# BaseNode.net
KiCad netlist of a schematic drawn in Altium Designer
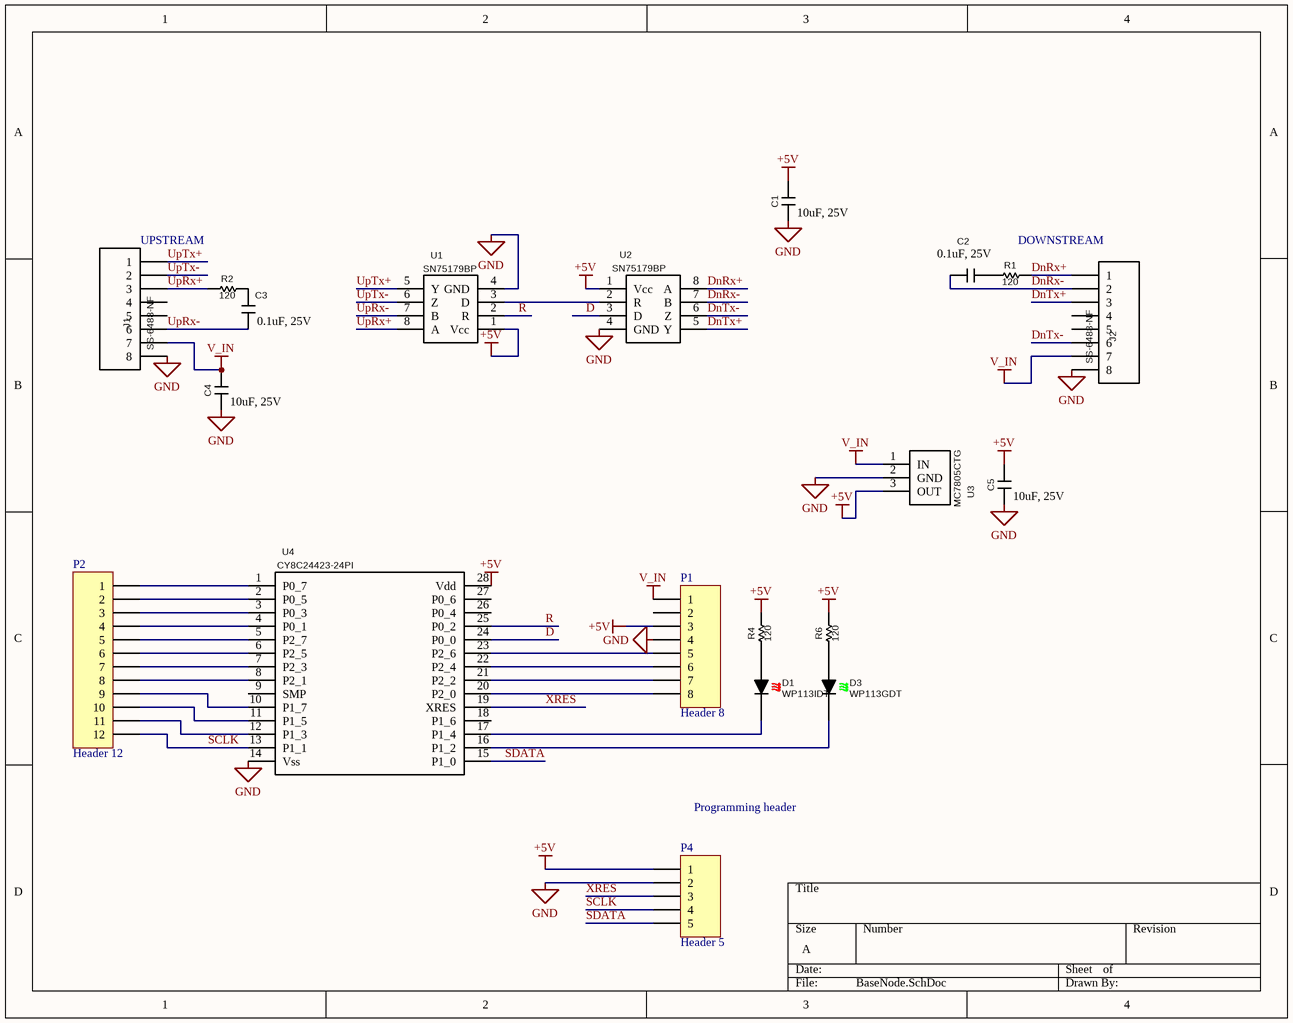
[diagram p0: BaseNode.SchDoc]

(export (version "E")
  (design (tool "Eeschema 10.0.6"))
  (components
    (comp (ref "C1")
      (value "10uF, 25V")
      (footprint "whong:Capacitor TH 0.2")
      (description "Capacitor")
      (fields (field (name "MANUFACTURER") "TDK Corporation"))
      (libsource (lib "whong") (part "Capacitor"))
    )
    (comp (ref "C2")
      (value "0.1uF, 25V")
      (footprint "whong:Capacitor TH 0.2")
      (description "Capacitor")
      (fields (field (name "MANUFACTURER") "Murata Electronics North America"))
      (libsource (lib "whong") (part "Capacitor"))
    )
    (comp (ref "C3")
      (value "0.1uF, 25V")
      (footprint "whong:Capacitor TH 0.2")
      (description "Capacitor")
      (fields (field (name "MANUFACTURER") "Murata Electronics North America"))
      (libsource (lib "whong") (part "Capacitor"))
    )
    (comp (ref "C4")
      (value "10uF, 25V")
      (footprint "whong:Capacitor TH 0.2")
      (description "Capacitor")
      (fields (field (name "MANUFACTURER") "TDK Corporation"))
      (libsource (lib "whong") (part "Capacitor"))
    )
    (comp (ref "C5")
      (value "10uF, 25V")
      (footprint "whong:Capacitor TH 0.2")
      (description "Capacitor")
      (fields (field (name "MANUFACTURER") "TDK Corporation"))
      (libsource (lib "whong") (part "Capacitor"))
    )
    (comp (ref "D1")
      (value "WP113IDT")
      (footprint "whong:LED 100mil")
      (description "LED RECT 2X5MM 625NM RED DIFF")
      (fields (field (name "MANUFACTURER") "Kingbright Corp") (field (name "MANUFACTURERPN") "WP113IDT"))
      (libsource (lib "whong") (part "WP113IDT"))
    )
    (comp (ref "D3")
      (value "WP113GDT")
      (footprint "whong:LED 100mil")
      (description "LED RECT 2X5MM 568NM GRN DIFF")
      (fields (field (name "MANUFACTURER") "Kingbright Corp") (field (name "MANUFACTURERPN") "WP113GDT"))
      (libsource (lib "whong") (part "WP113GDT"))
    )
    (comp (ref "J1")
      (value "SS-6488-NF")
      (footprint "whong:SS-6488-NF")
      (description "CONN 8-8 MOD JACK")
      (fields (field (name "MANUFACTURER") "Stewart Connector"))
      (libsource (lib "whong") (part "SS-6488-NF"))
    )
    (comp (ref "J2")
      (value "SS-6488-NF")
      (footprint "whong:SS-6488-NF")
      (description "CONN 8-8 MOD JACK")
      (fields (field (name "MANUFACTURER") "Stewart Connector"))
      (libsource (lib "") (part "SS-6488-NF_1"))
    )
    (comp (ref "P1")
      (value "Header 8")
      (footprint "HDR1X8")
      (description "Header, 8-Pin")
      (fields (field (name "PUBLISHER") "Altium Limited"))
      (libsource (lib "Miscellaneous Connectors") (part "Header 8"))
    )
    (comp (ref "P2")
      (value "Header 12")
      (footprint "HDR1X12")
      (description "Header, 12-Pin")
      (fields (field (name "PUBLISHER") "Altium Limited"))
      (libsource (lib "Miscellaneous Connectors") (part "Header 12"))
    )
    (comp (ref "P4")
      (value "Header 5")
      (footprint "HDR1X5")
      (description "Header, 5-Pin")
      (fields (field (name "PUBLISHER") "Altium Limited"))
      (libsource (lib "Miscellaneous Connectors") (part "Header 5"))
    )
    (comp (ref "R1")
      (value "120")
      (footprint "whong:Resistor Axial 100mil")
      (description "Resistor")
      (fields (field (name "MANUFACTURER") "Stackpole Electronics Inc") (field (name "TOLERANCE") "5%"))
      (libsource (lib "whong") (part "Resistor"))
    )
    (comp (ref "R2")
      (value "120")
      (footprint "whong:Resistor Axial 100mil")
      (description "Resistor")
      (fields (field (name "MANUFACTURER") "Stackpole Electronics Inc") (field (name "TOLERANCE") "5%"))
      (libsource (lib "whong") (part "Resistor"))
    )
    (comp (ref "R4")
      (value "120")
      (footprint "whong:Resistor Axial 100mil")
      (description "Resistor")
      (fields (field (name "MANUFACTURER") "Stackpole Electronics Inc") (field (name "TOLERANCE") "5%"))
      (libsource (lib "whong") (part "Resistor"))
    )
    (comp (ref "R6")
      (value "120")
      (footprint "whong:Resistor Axial 100mil")
      (description "Resistor")
      (fields (field (name "MANUFACTURER") "Stackpole Electronics Inc") (field (name "TOLERANCE") "5%"))
      (libsource (lib "whong") (part "Resistor"))
    )
    (comp (ref "U1")
      (value "SN75179BP")
      (footprint "dip8")
      (description "IC DIFF DRIVER/RECPAIR 8-DIP")
      (fields (field (name "MANUFACTURER") "Texas Instruments"))
      (libsource (lib "") (part "SN75179BP_1"))
    )
    (comp (ref "U2")
      (value "SN75179BP")
      (footprint "dip8")
      (description "IC DIFF DRIVER/RECPAIR 8-DIP")
      (fields (field (name "MANUFACTURER") "Texas Instruments"))
      (libsource (lib "whong") (part "SN75179BP"))
    )
    (comp (ref "U3")
      (value "MC7805CTG")
      (footprint "whong:TO-220")
      (description "IC REG VOLT POS 1A 5V TO220AB")
      (fields (field (name "MANUFACTURER") "ON Semiconductor"))
      (libsource (lib "whong") (part "MC7805CTG"))
    )
    (comp (ref "U4")
      (value "CY8C24423-24PI")
      (footprint "dip28")
      (description "IC MCU 4K FLASH 256B 28-DIP")
      (fields (field (name "MANUFACTURER") "Cypress Semiconductor Corp"))
      (libsource (lib "whong") (part "CY8C24423-24PI"))
    )
  )
  (nets
    (net (code "1") (name "+5V") (class "Default")
      (node (ref "C1") (pin "2") (pinfunction "2_2") (pintype "passive"))
      (node (ref "C5") (pin "2") (pinfunction "2_2") (pintype "passive"))
      (node (ref "P1") (pin "3") (pinfunction "3_3") (pintype "passive"))
      (node (ref "P4") (pin "1") (pinfunction "1_1") (pintype "passive"))
      (node (ref "R4") (pin "2") (pinfunction "2_2") (pintype "passive"))
      (node (ref "R6") (pin "2") (pinfunction "2_2") (pintype "passive"))
      (node (ref "U1") (pin "1") (pinfunction "Vcc_1") (pintype "passive"))
      (node (ref "U2") (pin "1") (pinfunction "Vcc_1") (pintype "passive"))
      (node (ref "U3") (pin "3") (pinfunction "OUT_3") (pintype "passive"))
      (node (ref "U4") (pin "28") (pinfunction "Vdd_28") (pintype "passive"))
    )
    (net (code "2") (name "/D") (class "Default")
      (node (ref "U2") (pin "3") (pinfunction "D_3") (pintype "passive"))
      (node (ref "U4") (pin "24") (pinfunction "P0_0_24") (pintype "passive"))
    )
    (net (code "3") (name "/DnRx+") (class "Default")
      (node (ref "J2") (pin "1") (pinfunction "1_1") (pintype "passive"))
      (node (ref "R1") (pin "2") (pinfunction "2_2") (pintype "passive"))
      (node (ref "U2") (pin "8") (pinfunction "A_8") (pintype "passive"))
    )
    (net (code "4") (name "/DnRx-") (class "Default")
      (node (ref "C2") (pin "2") (pinfunction "2_2") (pintype "passive"))
      (node (ref "J2") (pin "2") (pinfunction "2_2") (pintype "passive"))
      (node (ref "U2") (pin "7") (pinfunction "B_7") (pintype "passive"))
    )
    (net (code "5") (name "/DnTx+") (class "Default")
      (node (ref "J2") (pin "3") (pinfunction "3_3") (pintype "passive"))
      (node (ref "U2") (pin "5") (pinfunction "Y_5") (pintype "passive"))
    )
    (net (code "6") (name "/DnTx-") (class "Default")
      (node (ref "J2") (pin "6") (pinfunction "6_6") (pintype "passive"))
      (node (ref "U2") (pin "6") (pinfunction "Z_6") (pintype "passive"))
    )
    (net (code "7") (name "/R") (class "Default")
      (node (ref "U1") (pin "2") (pinfunction "R_2") (pintype "passive"))
      (node (ref "U4") (pin "25") (pinfunction "P0_2_25") (pintype "passive"))
    )
    (net (code "8") (name "/SCLK") (class "Default")
      (node (ref "P2") (pin "12") (pinfunction "12_12") (pintype "passive"))
      (node (ref "P4") (pin "4") (pinfunction "4_4") (pintype "passive"))
      (node (ref "U4") (pin "13") (pinfunction "P1_1_13") (pintype "passive"))
    )
    (net (code "9") (name "/SDATA") (class "Default")
      (node (ref "P4") (pin "5") (pinfunction "5_5") (pintype "passive"))
      (node (ref "U4") (pin "15") (pinfunction "P1_0_15") (pintype "passive"))
    )
    (net (code "10") (name "/UpRx+") (class "Default")
      (node (ref "J1") (pin "3") (pinfunction "3_3") (pintype "passive"))
      (node (ref "R2") (pin "1") (pinfunction "1_1") (pintype "passive"))
      (node (ref "U1") (pin "8") (pinfunction "A_8") (pintype "passive"))
    )
    (net (code "11") (name "/UpRx-") (class "Default")
      (node (ref "C3") (pin "1") (pinfunction "1_1") (pintype "passive"))
      (node (ref "J1") (pin "6") (pinfunction "6_6") (pintype "passive"))
      (node (ref "U1") (pin "7") (pinfunction "B_7") (pintype "passive"))
    )
    (net (code "12") (name "/UpTx+") (class "Default")
      (node (ref "J1") (pin "1") (pinfunction "1_1") (pintype "passive"))
      (node (ref "U1") (pin "5") (pinfunction "Y_5") (pintype "passive"))
    )
    (net (code "13") (name "/UpTx-") (class "Default")
      (node (ref "J1") (pin "2") (pinfunction "2_2") (pintype "passive"))
      (node (ref "U1") (pin "6") (pinfunction "Z_6") (pintype "passive"))
    )
    (net (code "14") (name "/XRES") (class "Default")
      (node (ref "P4") (pin "3") (pinfunction "3_3") (pintype "passive"))
      (node (ref "U4") (pin "19") (pinfunction "XRES_19") (pintype "passive"))
    )
    (net (code "15") (name "GND") (class "Default")
      (node (ref "C1") (pin "1") (pinfunction "1_1") (pintype "passive"))
      (node (ref "C4") (pin "1") (pinfunction "1_1") (pintype "passive"))
      (node (ref "C5") (pin "1") (pinfunction "1_1") (pintype "passive"))
      (node (ref "J1") (pin "8") (pinfunction "8_8") (pintype "passive"))
      (node (ref "J2") (pin "8") (pinfunction "8_8") (pintype "passive"))
      (node (ref "P1") (pin "4") (pinfunction "4_4") (pintype "passive"))
      (node (ref "P4") (pin "2") (pinfunction "2_2") (pintype "passive"))
      (node (ref "U1") (pin "4") (pinfunction "GND_4") (pintype "passive"))
      (node (ref "U2") (pin "4") (pinfunction "GND_4") (pintype "passive"))
      (node (ref "U3") (pin "2") (pinfunction "GND_2") (pintype "passive"))
      (node (ref "U4") (pin "14") (pinfunction "Vss_14") (pintype "passive"))
    )
    (net (code "16") (name "Net-(C2-Pad1)") (class "Default")
      (node (ref "C2") (pin "1") (pinfunction "1_1") (pintype "passive"))
      (node (ref "R1") (pin "1") (pinfunction "1_1") (pintype "passive"))
    )
    (net (code "17") (name "Net-(C3-Pad2)") (class "Default")
      (node (ref "C3") (pin "2") (pinfunction "2_2") (pintype "passive"))
      (node (ref "R2") (pin "2") (pinfunction "2_2") (pintype "passive"))
    )
    (net (code "18") (name "Net-(D1-PadA)") (class "Default")
      (node (ref "D1") (pin "A") (pinfunction "A_A") (pintype "passive"))
      (node (ref "R4") (pin "1") (pinfunction "1_1") (pintype "passive"))
    )
    (net (code "19") (name "Net-(D3-PadA)") (class "Default")
      (node (ref "D3") (pin "A") (pinfunction "A_A") (pintype "passive"))
      (node (ref "R6") (pin "1") (pinfunction "1_1") (pintype "passive"))
    )
    (net (code "20") (name "Net-(U1-D)") (class "Default")
      (node (ref "U1") (pin "3") (pinfunction "D_3") (pintype "passive"))
      (node (ref "U2") (pin "2") (pinfunction "R_2") (pintype "passive"))
    )
    (net (code "21") (name "Net-(U4-P0_1)") (class "Default")
      (node (ref "P2") (pin "4") (pinfunction "4_4") (pintype "passive"))
      (node (ref "U4") (pin "4") (pinfunction "P0_1_4") (pintype "passive"))
    )
    (net (code "22") (name "Net-(U4-P0_3)") (class "Default")
      (node (ref "P2") (pin "3") (pinfunction "3_3") (pintype "passive"))
      (node (ref "U4") (pin "3") (pinfunction "P0_3_3") (pintype "passive"))
    )
    (net (code "23") (name "Net-(U4-P0_5)") (class "Default")
      (node (ref "P2") (pin "2") (pinfunction "2_2") (pintype "passive"))
      (node (ref "U4") (pin "2") (pinfunction "P0_5_2") (pintype "passive"))
    )
    (net (code "24") (name "Net-(U4-P0_7)") (class "Default")
      (node (ref "P2") (pin "1") (pinfunction "1_1") (pintype "passive"))
      (node (ref "U4") (pin "1") (pinfunction "P0_7_1") (pintype "passive"))
    )
    (net (code "25") (name "Net-(U4-P1_2)") (class "Default")
      (node (ref "D3") (pin "K") (pinfunction "K_K") (pintype "passive"))
      (node (ref "U4") (pin "16") (pinfunction "P1_2_16") (pintype "passive"))
    )
    (net (code "26") (name "Net-(U4-P1_3)") (class "Default")
      (node (ref "P2") (pin "11") (pinfunction "11_11") (pintype "passive"))
      (node (ref "U4") (pin "12") (pinfunction "P1_3_12") (pintype "passive"))
    )
    (net (code "27") (name "Net-(U4-P1_4)") (class "Default")
      (node (ref "D1") (pin "K") (pinfunction "K_K") (pintype "passive"))
      (node (ref "U4") (pin "17") (pinfunction "P1_4_17") (pintype "passive"))
    )
    (net (code "28") (name "Net-(U4-P1_5)") (class "Default")
      (node (ref "P2") (pin "10") (pinfunction "10_10") (pintype "passive"))
      (node (ref "U4") (pin "11") (pinfunction "P1_5_11") (pintype "passive"))
    )
    (net (code "29") (name "Net-(U4-P1_7)") (class "Default")
      (node (ref "P2") (pin "9") (pinfunction "9_9") (pintype "passive"))
      (node (ref "U4") (pin "10") (pinfunction "P1_7_10") (pintype "passive"))
    )
    (net (code "30") (name "Net-(U4-P2_0)") (class "Default")
      (node (ref "P1") (pin "8") (pinfunction "8_8") (pintype "passive"))
      (node (ref "U4") (pin "20") (pinfunction "P2_0_20") (pintype "passive"))
    )
    (net (code "31") (name "Net-(U4-P2_1)") (class "Default")
      (node (ref "P2") (pin "8") (pinfunction "8_8") (pintype "passive"))
      (node (ref "U4") (pin "8") (pinfunction "P2_1_8") (pintype "passive"))
    )
    (net (code "32") (name "Net-(U4-P2_2)") (class "Default")
      (node (ref "P1") (pin "7") (pinfunction "7_7") (pintype "passive"))
      (node (ref "U4") (pin "21") (pinfunction "P2_2_21") (pintype "passive"))
    )
    (net (code "33") (name "Net-(U4-P2_3)") (class "Default")
      (node (ref "P2") (pin "7") (pinfunction "7_7") (pintype "passive"))
      (node (ref "U4") (pin "7") (pinfunction "P2_3_7") (pintype "passive"))
    )
    (net (code "34") (name "Net-(U4-P2_4)") (class "Default")
      (node (ref "P1") (pin "6") (pinfunction "6_6") (pintype "passive"))
      (node (ref "U4") (pin "22") (pinfunction "P2_4_22") (pintype "passive"))
    )
    (net (code "35") (name "Net-(U4-P2_5)") (class "Default")
      (node (ref "P2") (pin "6") (pinfunction "6_6") (pintype "passive"))
      (node (ref "U4") (pin "6") (pinfunction "P2_5_6") (pintype "passive"))
    )
    (net (code "36") (name "Net-(U4-P2_6)") (class "Default")
      (node (ref "P1") (pin "5") (pinfunction "5_5") (pintype "passive"))
      (node (ref "U4") (pin "23") (pinfunction "P2_6_23") (pintype "passive"))
    )
    (net (code "37") (name "Net-(U4-P2_7)") (class "Default")
      (node (ref "P2") (pin "5") (pinfunction "5_5") (pintype "passive"))
      (node (ref "U4") (pin "5") (pinfunction "P2_7_5") (pintype "passive"))
    )
    (net (code "38") (name "V_IN") (class "Default")
      (node (ref "C4") (pin "2") (pinfunction "2_2") (pintype "passive"))
      (node (ref "J1") (pin "7") (pinfunction "7_7") (pintype "passive"))
      (node (ref "J2") (pin "7") (pinfunction "7_7") (pintype "passive"))
      (node (ref "P1") (pin "1") (pinfunction "1_1") (pintype "passive"))
      (node (ref "U3") (pin "1") (pinfunction "IN_1") (pintype "passive"))
    )
    (net (code "39") (name "unconnected-(J1-Pad4)") (class "Default")
      (node (ref "J1") (pin "4") (pinfunction "4_4") (pintype "passive"))
    )
    (net (code "40") (name "unconnected-(J1-Pad5)") (class "Default")
      (node (ref "J1") (pin "5") (pinfunction "5_5") (pintype "passive"))
    )
    (net (code "41") (name "unconnected-(J2-Pad4)") (class "Default")
      (node (ref "J2") (pin "4") (pinfunction "4_4") (pintype "passive"))
    )
    (net (code "42") (name "unconnected-(J2-Pad5)") (class "Default")
      (node (ref "J2") (pin "5") (pinfunction "5_5") (pintype "passive"))
    )
    (net (code "43") (name "unconnected-(P1-Pad2)") (class "Default")
      (node (ref "P1") (pin "2") (pinfunction "2_2") (pintype "passive"))
    )
    (net (code "44") (name "unconnected-(U4-P0_4-Pad26)") (class "Default")
      (node (ref "U4") (pin "26") (pinfunction "P0_4_26") (pintype "passive"))
    )
    (net (code "45") (name "unconnected-(U4-P0_6-Pad27)") (class "Default")
      (node (ref "U4") (pin "27") (pinfunction "P0_6_27") (pintype "passive"))
    )
    (net (code "46") (name "unconnected-(U4-P1_6-Pad18)") (class "Default")
      (node (ref "U4") (pin "18") (pinfunction "P1_6_18") (pintype "passive"))
    )
    (net (code "47") (name "unconnected-(U4-SMP-Pad9)") (class "Default")
      (node (ref "U4") (pin "9") (pinfunction "SMP_9") (pintype "passive"))
    )
  )
)
